# Stepper_driver_diff.net
KiCad netlist of a schematic drawn in Altium Designer
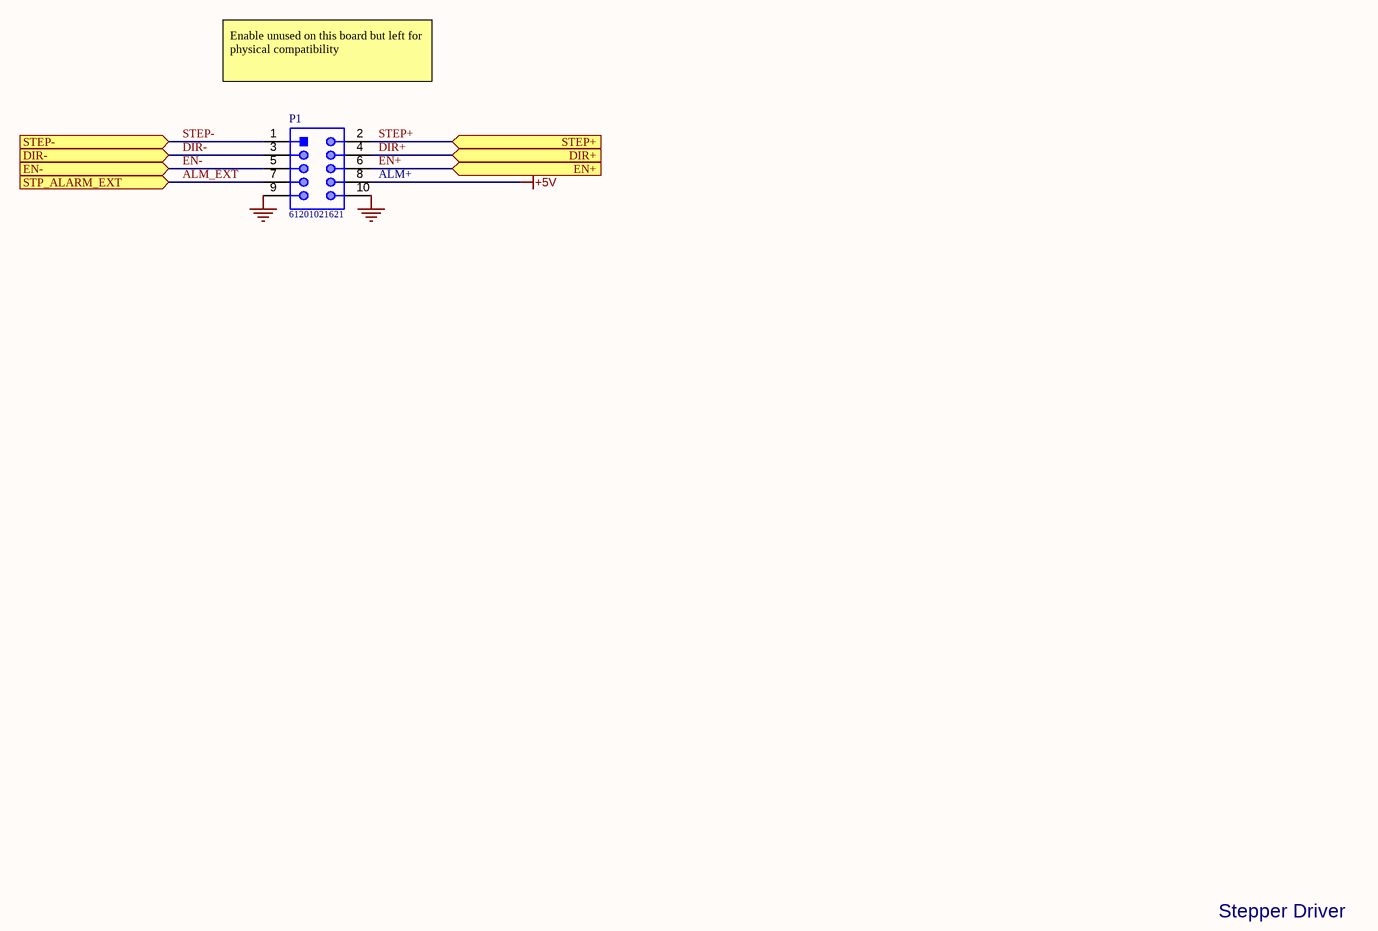
[diagram p0: Stepper_driver_diff.SchDoc]

(export (version "E")
  (design (tool "Eeschema 10.0.6"))
  (components
    (comp (ref "P1")
      (value "61201021621")
      (footprint "61201021621")
      (description "Male Box Header WR-BHD, THT, Vertical, pitch 2.54 mm, 10 pins")
      (fields (field (name "MANUFACTURER") "Wurth Elektronik") (field (name "PUBLISHER") "WurthElektronik"))
      (libsource (lib "Altium Content Vault") (part "WE-CN-2P-M-R10"))
    )
  )
  (nets
    (net (code "1") (name "+5V") (class "Default")
      (node (ref "P1") (pin "8") (pinfunction "8_8") (pintype "passive"))
    )
    (net (code "2") (name "/ALM_EXT") (class "Default")
      (node (ref "P1") (pin "7") (pinfunction "7_7") (pintype "passive"))
    )
    (net (code "3") (name "/DIR+") (class "Default")
      (node (ref "P1") (pin "4") (pinfunction "4_4") (pintype "passive"))
    )
    (net (code "4") (name "/DIR-") (class "Default")
      (node (ref "P1") (pin "3") (pinfunction "3_3") (pintype "passive"))
    )
    (net (code "5") (name "/EN+") (class "Default")
      (node (ref "P1") (pin "6") (pinfunction "6_6") (pintype "passive"))
    )
    (net (code "6") (name "/EN-") (class "Default")
      (node (ref "P1") (pin "5") (pinfunction "5_5") (pintype "passive"))
    )
    (net (code "7") (name "/STEP+") (class "Default")
      (node (ref "P1") (pin "2") (pinfunction "2_2") (pintype "passive"))
    )
    (net (code "8") (name "/STEP-") (class "Default")
      (node (ref "P1") (pin "1") (pinfunction "1_1") (pintype "passive"))
    )
    (net (code "9") (name "GND") (class "Default")
      (node (ref "P1") (pin "10") (pinfunction "10_10") (pintype "passive"))
      (node (ref "P1") (pin "9") (pinfunction "9_9") (pintype "passive"))
    )
  )
)
